# amplifier-chain.net
KiCad netlist of a schematic drawn in Altium Designer
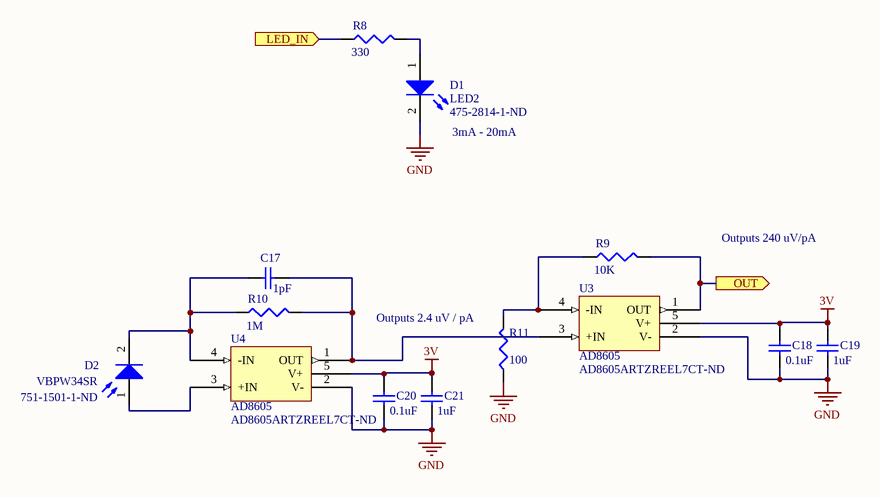
[diagram p0: amplifier-chain.SchDoc]

(export (version "E")
  (design (tool "Eeschema 10.0.6"))
  (components
    (comp (ref "C17")
      (value "1pF")
      (footprint "1608[0603]")
      (description "Capacitor (Semiconductor SIM Model)")
      (fields (field (name "PUBLISHER") "Altium Limited"))
      (libsource (lib "Miscellaneous Devices") (part "Cap Semi"))
    )
    (comp (ref "C18")
      (value "0.1uF")
      (footprint "1608[0603]")
      (description "Capacitor (Semiconductor SIM Model)")
      (fields (field (name "PUBLISHER") "Altium Limited"))
      (libsource (lib "Miscellaneous Devices") (part "Cap Semi"))
    )
    (comp (ref "C19")
      (value "1uF")
      (footprint "1608[0603]")
      (description "Capacitor (Semiconductor SIM Model)")
      (fields (field (name "PUBLISHER") "Altium Limited"))
      (libsource (lib "Miscellaneous Devices") (part "Cap Semi"))
    )
    (comp (ref "C20")
      (value "0.1uF")
      (footprint "1608[0603]")
      (description "Capacitor (Semiconductor SIM Model)")
      (fields (field (name "PUBLISHER") "Altium Limited"))
      (libsource (lib "Miscellaneous Devices") (part "Cap Semi"))
    )
    (comp (ref "C21")
      (value "1uF")
      (footprint "1608[0603]")
      (description "Capacitor (Semiconductor SIM Model)")
      (fields (field (name "PUBLISHER") "Altium Limited"))
      (libsource (lib "Miscellaneous Devices") (part "Cap Semi"))
    )
    (comp (ref "D1")
      (value "LED2")
      (footprint "LB P4SG")
      (description "Typical RED, GREEN, YELLOW, AMBER GaAs LED")
      (fields
        (field (name "SUPPLIER PART NUMBER") "475-2814-1-ND")
        (field (name "PUBLISHER") "Altium Limited")
      )
      (libsource (lib "Miscellaneous Devices") (part "LED2"))
    )
    (comp (ref "D2")
      (value "VBPW34SR")
      (footprint "VBPW34SR")
      (description "Photosensitive Diode")
      (fields
        (field (name "SUPPLIER PART NUMBER") "751-1501-1-ND")
        (field (name "PUBLISHER") "Altium Limited")
      )
      (libsource (lib "Miscellaneous Devices") (part "Photo Sen"))
    )
    (comp (ref "R8")
      (value "330")
      (footprint "J1-0603")
      (description "Resistor")
      (fields (field (name "PUBLISHER") "Altium Limited"))
      (libsource (lib "Miscellaneous Devices") (part "Res3"))
    )
    (comp (ref "R9")
      (value "10K")
      (footprint "J1-0603")
      (description "Resistor")
      (fields (field (name "PUBLISHER") "Altium Limited"))
      (libsource (lib "Miscellaneous Devices") (part "Res3"))
    )
    (comp (ref "R10")
      (value "1M")
      (footprint "J1-0603")
      (description "Resistor")
      (fields (field (name "PUBLISHER") "Altium Limited"))
      (libsource (lib "Miscellaneous Devices") (part "Res3"))
    )
    (comp (ref "R11")
      (value "100")
      (footprint "J1-0603")
      (description "Resistor")
      (fields (field (name "PUBLISHER") "Altium Limited"))
      (libsource (lib "Miscellaneous Devices") (part "Res3"))
    )
    (comp (ref "U3")
      (value "AD8605")
      (footprint "SOT23-6_N")
      (description "Low noise, precision rail-to-rail op-amp.")
      (fields (field (name "SUPPLIER PART NUMBER 1") "AD8605ARTZREEL7CT-ND"))
      (libsource (lib "PAY") (part "AD8605"))
    )
    (comp (ref "U4")
      (value "AD8605")
      (footprint "SOT23-6_N")
      (description "Low noise, precision rail-to-rail op-amp.")
      (fields (field (name "SUPPLIER PART NUMBER 1") "AD8605ARTZREEL7CT-ND"))
      (libsource (lib "PAY") (part "AD8605"))
    )
  )
  (nets
    (net (code "1") (name "/LED_IN") (class "Default")
      (node (ref "R8") (pin "1") (pinfunction "1_1") (pintype "passive"))
    )
    (net (code "2") (name "/OUT") (class "Default")
      (node (ref "R9") (pin "2") (pinfunction "2_2") (pintype "passive"))
      (node (ref "U3") (pin "1") (pinfunction "OUT_1") (pintype "output"))
    )
    (net (code "3") (name "3V") (class "Default")
      (node (ref "C18") (pin "2") (pinfunction "2_2") (pintype "passive"))
      (node (ref "C19") (pin "2") (pinfunction "2_2") (pintype "passive"))
      (node (ref "C20") (pin "2") (pinfunction "2_2") (pintype "passive"))
      (node (ref "C21") (pin "2") (pinfunction "2_2") (pintype "passive"))
      (node (ref "U3") (pin "5") (pinfunction "V+_5") (pintype "power_in"))
      (node (ref "U4") (pin "5") (pinfunction "V+_5") (pintype "power_in"))
    )
    (net (code "4") (name "GND") (class "Default")
      (node (ref "C18") (pin "1") (pinfunction "1_1") (pintype "passive"))
      (node (ref "C19") (pin "1") (pinfunction "1_1") (pintype "passive"))
      (node (ref "C20") (pin "1") (pinfunction "1_1") (pintype "passive"))
      (node (ref "C21") (pin "1") (pinfunction "1_1") (pintype "passive"))
      (node (ref "D1") (pin "2") (pinfunction "K_2") (pintype "passive"))
      (node (ref "R11") (pin "1") (pinfunction "1_1") (pintype "passive"))
      (node (ref "U3") (pin "2") (pinfunction "V-_2") (pintype "power_in"))
      (node (ref "U4") (pin "2") (pinfunction "V-_2") (pintype "power_in"))
    )
    (net (code "5") (name "Net-(D1-A)") (class "Default")
      (node (ref "D1") (pin "1") (pinfunction "A_1") (pintype "passive"))
      (node (ref "R8") (pin "2") (pinfunction "2_2") (pintype "passive"))
    )
    (net (code "6") (name "Net-(D2-A)") (class "Default")
      (node (ref "D2") (pin "1") (pinfunction "A_1") (pintype "passive"))
      (node (ref "U4") (pin "3") (pinfunction "+IN_3") (pintype "input"))
    )
    (net (code "7") (name "Net-(D2-K)") (class "Default")
      (node (ref "C17") (pin "1") (pinfunction "1_1") (pintype "passive"))
      (node (ref "D2") (pin "2") (pinfunction "K_2") (pintype "passive"))
      (node (ref "R10") (pin "1") (pinfunction "1_1") (pintype "passive"))
      (node (ref "U4") (pin "4") (pinfunction "-IN_4") (pintype "input"))
    )
    (net (code "8") (name "Net-(U3-+IN)") (class "Default")
      (node (ref "C17") (pin "2") (pinfunction "2_2") (pintype "passive"))
      (node (ref "R10") (pin "2") (pinfunction "2_2") (pintype "passive"))
      (node (ref "U3") (pin "3") (pinfunction "+IN_3") (pintype "input"))
      (node (ref "U4") (pin "1") (pinfunction "OUT_1") (pintype "output"))
    )
    (net (code "9") (name "Net-(U3--IN)") (class "Default")
      (node (ref "R11") (pin "2") (pinfunction "2_2") (pintype "passive"))
      (node (ref "R9") (pin "1") (pinfunction "1_1") (pintype "passive"))
      (node (ref "U3") (pin "4") (pinfunction "-IN_4") (pintype "input"))
    )
  )
)
